# Part15_I2C_LED.net
KiCad netlist of a schematic drawn in Altium Designer
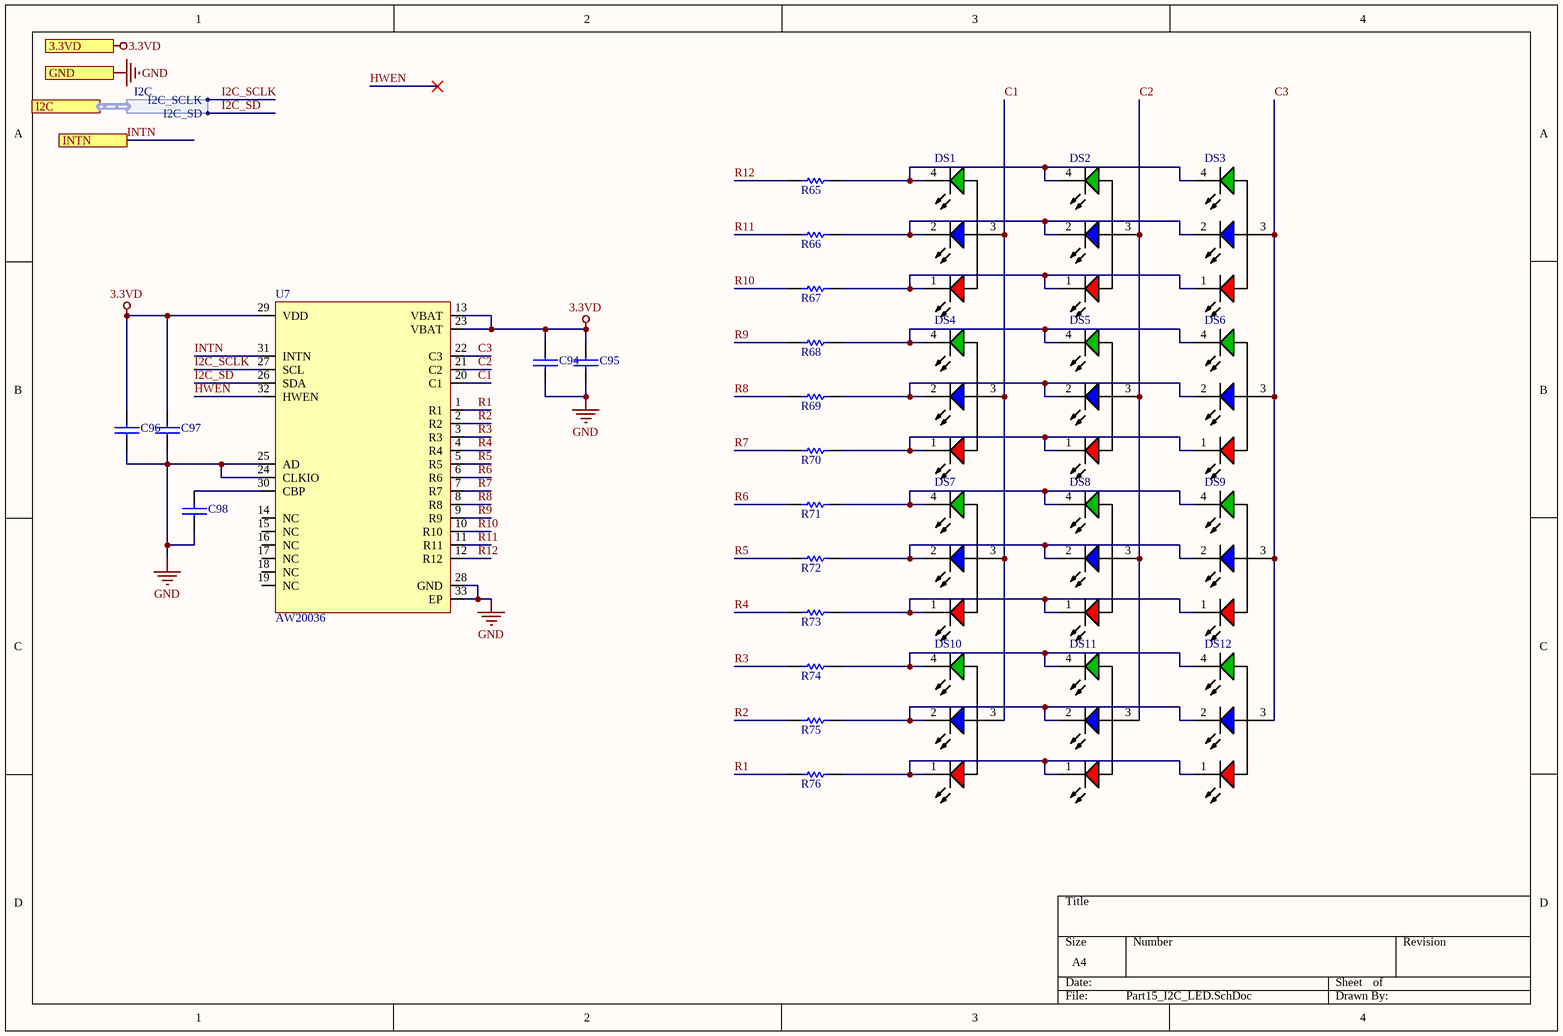
[diagram p0: Part15_I2C_LED.SchDoc]

(export (version "E")
  (design (tool "Eeschema 10.0.6"))
  (components
    (comp (ref "C94")
      (value "100nF")
      (footprint "0402C")
      (description "无极性电容")
      (libsource (lib "电容") (part "CAP"))
    )
    (comp (ref "C95")
      (value "4.7uF")
      (footprint "0402C")
      (description "无极性电容")
      (libsource (lib "电容") (part "CAP"))
    )
    (comp (ref "C96")
      (value "1uF")
      (footprint "0402C")
      (description "无极性电容")
      (libsource (lib "电容") (part "CAP"))
    )
    (comp (ref "C97")
      (value "100nF")
      (footprint "0402C")
      (description "无极性电容")
      (libsource (lib "电容") (part "CAP"))
    )
    (comp (ref "C98")
      (value "1uF")
      (footprint "0402C")
      (description "无极性电容")
      (libsource (lib "电容") (part "CAP"))
    )
    (comp (ref "DS1")
      (value "CLVBA-FKA-CAEDH8BBB7A363")
      (footprint "RGB_LED")
      (description "3-in-1 SMD Led, 1.9 V Red, 3 V Green, 3 V Blue, -40 to 100 degC, 4-Pin PLCC, RoHS, Reel")
      (fields (field (name "MANUFACTURER") "Cree,Inc."))
      (libsource (lib "MT7688_Lib") (part "LED-RGB-KCKK-4"))
    )
    (comp (ref "DS2")
      (value "CLVBA-FKA-CAEDH8BBB7A363")
      (footprint "RGB_LED")
      (description "3-in-1 SMD Led, 1.9 V Red, 3 V Green, 3 V Blue, -40 to 100 degC, 4-Pin PLCC, RoHS, Reel")
      (fields (field (name "MANUFACTURER") "Cree,Inc."))
      (libsource (lib "MT7688_Lib") (part "LED-RGB-KCKK-4"))
    )
    (comp (ref "DS3")
      (value "CLVBA-FKA-CAEDH8BBB7A363")
      (footprint "RGB_LED")
      (description "3-in-1 SMD Led, 1.9 V Red, 3 V Green, 3 V Blue, -40 to 100 degC, 4-Pin PLCC, RoHS, Reel")
      (fields (field (name "MANUFACTURER") "Cree,Inc."))
      (libsource (lib "MT7688_Lib") (part "LED-RGB-KCKK-4"))
    )
    (comp (ref "DS4")
      (value "CLVBA-FKA-CAEDH8BBB7A363")
      (footprint "RGB_LED")
      (description "3-in-1 SMD Led, 1.9 V Red, 3 V Green, 3 V Blue, -40 to 100 degC, 4-Pin PLCC, RoHS, Reel")
      (fields (field (name "MANUFACTURER") "Cree,Inc."))
      (libsource (lib "MT7688_Lib") (part "LED-RGB-KCKK-4"))
    )
    (comp (ref "DS5")
      (value "CLVBA-FKA-CAEDH8BBB7A363")
      (footprint "RGB_LED")
      (description "3-in-1 SMD Led, 1.9 V Red, 3 V Green, 3 V Blue, -40 to 100 degC, 4-Pin PLCC, RoHS, Reel")
      (fields (field (name "MANUFACTURER") "Cree,Inc."))
      (libsource (lib "MT7688_Lib") (part "LED-RGB-KCKK-4"))
    )
    (comp (ref "DS6")
      (value "CLVBA-FKA-CAEDH8BBB7A363")
      (footprint "RGB_LED")
      (description "3-in-1 SMD Led, 1.9 V Red, 3 V Green, 3 V Blue, -40 to 100 degC, 4-Pin PLCC, RoHS, Reel")
      (fields (field (name "MANUFACTURER") "Cree,Inc."))
      (libsource (lib "MT7688_Lib") (part "LED-RGB-KCKK-4"))
    )
    (comp (ref "DS7")
      (value "CLVBA-FKA-CAEDH8BBB7A363")
      (footprint "RGB_LED")
      (description "3-in-1 SMD Led, 1.9 V Red, 3 V Green, 3 V Blue, -40 to 100 degC, 4-Pin PLCC, RoHS, Reel")
      (fields (field (name "MANUFACTURER") "Cree,Inc."))
      (libsource (lib "MT7688_Lib") (part "LED-RGB-KCKK-4"))
    )
    (comp (ref "DS8")
      (value "CLVBA-FKA-CAEDH8BBB7A363")
      (footprint "RGB_LED")
      (description "3-in-1 SMD Led, 1.9 V Red, 3 V Green, 3 V Blue, -40 to 100 degC, 4-Pin PLCC, RoHS, Reel")
      (fields (field (name "MANUFACTURER") "Cree,Inc."))
      (libsource (lib "MT7688_Lib") (part "LED-RGB-KCKK-4"))
    )
    (comp (ref "DS9")
      (value "CLVBA-FKA-CAEDH8BBB7A363")
      (footprint "RGB_LED")
      (description "3-in-1 SMD Led, 1.9 V Red, 3 V Green, 3 V Blue, -40 to 100 degC, 4-Pin PLCC, RoHS, Reel")
      (fields (field (name "MANUFACTURER") "Cree,Inc."))
      (libsource (lib "MT7688_Lib") (part "LED-RGB-KCKK-4"))
    )
    (comp (ref "DS10")
      (value "CLVBA-FKA-CAEDH8BBB7A363")
      (footprint "RGB_LED")
      (description "3-in-1 SMD Led, 1.9 V Red, 3 V Green, 3 V Blue, -40 to 100 degC, 4-Pin PLCC, RoHS, Reel")
      (fields (field (name "MANUFACTURER") "Cree,Inc."))
      (libsource (lib "MT7688_Lib") (part "LED-RGB-KCKK-4"))
    )
    (comp (ref "DS11")
      (value "CLVBA-FKA-CAEDH8BBB7A363")
      (footprint "RGB_LED")
      (description "3-in-1 SMD Led, 1.9 V Red, 3 V Green, 3 V Blue, -40 to 100 degC, 4-Pin PLCC, RoHS, Reel")
      (fields (field (name "MANUFACTURER") "Cree,Inc."))
      (libsource (lib "MT7688_Lib") (part "LED-RGB-KCKK-4"))
    )
    (comp (ref "DS12")
      (value "CLVBA-FKA-CAEDH8BBB7A363")
      (footprint "RGB_LED")
      (description "3-in-1 SMD Led, 1.9 V Red, 3 V Green, 3 V Blue, -40 to 100 degC, 4-Pin PLCC, RoHS, Reel")
      (fields (field (name "MANUFACTURER") "Cree,Inc."))
      (libsource (lib "MT7688_Lib") (part "LED-RGB-KCKK-4"))
    )
    (comp (ref "R65") (value "51R") (footprint "0402R") (libsource (lib "电阻") (part "RES")))
    (comp (ref "R66") (value "20R") (footprint "0402R") (libsource (lib "电阻") (part "RES")))
    (comp (ref "R67") (value "20R") (footprint "0402R") (libsource (lib "电阻") (part "RES")))
    (comp (ref "R68") (value "51R") (footprint "0402R") (libsource (lib "电阻") (part "RES")))
    (comp (ref "R69") (value "20R") (footprint "0402R") (libsource (lib "电阻") (part "RES")))
    (comp (ref "R70") (value "20R") (footprint "0402R") (libsource (lib "电阻") (part "RES")))
    (comp (ref "R71") (value "51R") (footprint "0402R") (libsource (lib "电阻") (part "RES")))
    (comp (ref "R72") (value "20R") (footprint "0402R") (libsource (lib "电阻") (part "RES")))
    (comp (ref "R73") (value "20R") (footprint "0402R") (libsource (lib "电阻") (part "RES")))
    (comp (ref "R74") (value "51R") (footprint "0402R") (libsource (lib "电阻") (part "RES")))
    (comp (ref "R75") (value "20R") (footprint "0402R") (libsource (lib "电阻") (part "RES")))
    (comp (ref "R76") (value "20R") (footprint "0402R") (libsource (lib "电阻") (part "RES")))
    (comp (ref "U7")
      (value "AW20036")
      (footprint "QFN40P400X400X80_HS-33N")
      (libsource (lib "MT7688_Lib") (part "AW20036"))
    )
  )
  (nets
    (net (code "2") (name "/C1") (class "Default")
      (node (ref "DS1") (pin "3") (pinfunction "COMMON_3") (pintype "passive"))
      (node (ref "DS10") (pin "3") (pinfunction "COMMON_3") (pintype "passive"))
      (node (ref "DS4") (pin "3") (pinfunction "COMMON_3") (pintype "passive"))
      (node (ref "DS7") (pin "3") (pinfunction "COMMON_3") (pintype "passive"))
      (node (ref "U7") (pin "20") (pinfunction "C1_20") (pintype "passive"))
    )
    (net (code "3") (name "/C2") (class "Default")
      (node (ref "DS11") (pin "3") (pinfunction "COMMON_3") (pintype "passive"))
      (node (ref "DS2") (pin "3") (pinfunction "COMMON_3") (pintype "passive"))
      (node (ref "DS5") (pin "3") (pinfunction "COMMON_3") (pintype "passive"))
      (node (ref "DS8") (pin "3") (pinfunction "COMMON_3") (pintype "passive"))
      (node (ref "U7") (pin "21") (pinfunction "C2_21") (pintype "passive"))
    )
    (net (code "4") (name "/C3") (class "Default")
      (node (ref "DS12") (pin "3") (pinfunction "COMMON_3") (pintype "passive"))
      (node (ref "DS3") (pin "3") (pinfunction "COMMON_3") (pintype "passive"))
      (node (ref "DS6") (pin "3") (pinfunction "COMMON_3") (pintype "passive"))
      (node (ref "DS9") (pin "3") (pinfunction "COMMON_3") (pintype "passive"))
      (node (ref "U7") (pin "22") (pinfunction "C3_22") (pintype "passive"))
    )
    (net (code "5") (name "/HWEN") (class "Default")
      (node (ref "U7") (pin "32") (pinfunction "HWEN_32") (pintype "passive"))
    )
    (net (code "6") (name "/I2C_SCLK") (class "Default")
      (node (ref "U7") (pin "27") (pinfunction "SCL_27") (pintype "passive"))
    )
    (net (code "7") (name "/I2C_SD") (class "Default")
      (node (ref "U7") (pin "26") (pinfunction "SDA_26") (pintype "passive"))
    )
    (net (code "8") (name "/INTN") (class "Default")
      (node (ref "U7") (pin "31") (pinfunction "INTN_31") (pintype "passive"))
    )
    (net (code "9") (name "/R1") (class "Default")
      (node (ref "R76") (pin "1") (pinfunction "1_1") (pintype "passive"))
      (node (ref "U7") (pin "1") (pinfunction "R1_1") (pintype "passive"))
    )
    (net (code "10") (name "/R2") (class "Default")
      (node (ref "R75") (pin "1") (pinfunction "1_1") (pintype "passive"))
      (node (ref "U7") (pin "2") (pinfunction "R2_2") (pintype "passive"))
    )
    (net (code "11") (name "/R3") (class "Default")
      (node (ref "R74") (pin "1") (pinfunction "1_1") (pintype "passive"))
      (node (ref "U7") (pin "3") (pinfunction "R3_3") (pintype "passive"))
    )
    (net (code "12") (name "/R4") (class "Default")
      (node (ref "R73") (pin "1") (pinfunction "1_1") (pintype "passive"))
      (node (ref "U7") (pin "4") (pinfunction "R4_4") (pintype "passive"))
    )
    (net (code "13") (name "/R5") (class "Default")
      (node (ref "R72") (pin "1") (pinfunction "1_1") (pintype "passive"))
      (node (ref "U7") (pin "5") (pinfunction "R5_5") (pintype "passive"))
    )
    (net (code "14") (name "/R6") (class "Default")
      (node (ref "R71") (pin "1") (pinfunction "1_1") (pintype "passive"))
      (node (ref "U7") (pin "6") (pinfunction "R6_6") (pintype "passive"))
    )
    (net (code "15") (name "/R7") (class "Default")
      (node (ref "R70") (pin "1") (pinfunction "1_1") (pintype "passive"))
      (node (ref "U7") (pin "7") (pinfunction "R7_7") (pintype "passive"))
    )
    (net (code "16") (name "/R8") (class "Default")
      (node (ref "R69") (pin "1") (pinfunction "1_1") (pintype "passive"))
      (node (ref "U7") (pin "8") (pinfunction "R8_8") (pintype "passive"))
    )
    (net (code "17") (name "/R9") (class "Default")
      (node (ref "R68") (pin "1") (pinfunction "1_1") (pintype "passive"))
      (node (ref "U7") (pin "9") (pinfunction "R9_9") (pintype "passive"))
    )
    (net (code "18") (name "/R10") (class "Default")
      (node (ref "R67") (pin "1") (pinfunction "1_1") (pintype "passive"))
      (node (ref "U7") (pin "10") (pinfunction "R10_10") (pintype "passive"))
    )
    (net (code "19") (name "/R11") (class "Default")
      (node (ref "R66") (pin "1") (pinfunction "1_1") (pintype "passive"))
      (node (ref "U7") (pin "11") (pinfunction "R11_11") (pintype "passive"))
    )
    (net (code "20") (name "/R12") (class "Default")
      (node (ref "R65") (pin "1") (pinfunction "1_1") (pintype "passive"))
      (node (ref "U7") (pin "12") (pinfunction "R12_12") (pintype "passive"))
    )
    (net (code "22") (name "3.3VD") (class "Default")
      (node (ref "C94") (pin "1") (pinfunction "1_1") (pintype "passive"))
      (node (ref "C95") (pin "1") (pinfunction "1_1") (pintype "passive"))
      (node (ref "C96") (pin "1") (pinfunction "1_1") (pintype "passive"))
      (node (ref "C97") (pin "1") (pinfunction "1_1") (pintype "passive"))
      (node (ref "U7") (pin "13") (pinfunction "VBAT_13") (pintype "passive"))
      (node (ref "U7") (pin "23") (pinfunction "VBAT_23") (pintype "passive"))
      (node (ref "U7") (pin "29") (pinfunction "VDD_29") (pintype "passive"))
    )
    (net (code "23") (name "GND") (class "Default")
      (node (ref "C94") (pin "2") (pinfunction "2_2") (pintype "passive"))
      (node (ref "C95") (pin "2") (pinfunction "2_2") (pintype "passive"))
      (node (ref "C96") (pin "2") (pinfunction "2_2") (pintype "passive"))
      (node (ref "C97") (pin "2") (pinfunction "2_2") (pintype "passive"))
      (node (ref "C98") (pin "2") (pinfunction "2_2") (pintype "passive"))
      (node (ref "U7") (pin "24") (pinfunction "CLKIO_24") (pintype "passive"))
      (node (ref "U7") (pin "25") (pinfunction "AD_25") (pintype "passive"))
      (node (ref "U7") (pin "28") (pinfunction "GND_28") (pintype "passive"))
      (node (ref "U7") (pin "33") (pinfunction "EP_33") (pintype "passive"))
    )
    (net (code "24") (name "Net-(DS1-BLUE)") (class "Default")
      (node (ref "DS1") (pin "2") (pinfunction "BLUE_2") (pintype "passive"))
      (node (ref "DS2") (pin "2") (pinfunction "BLUE_2") (pintype "passive"))
      (node (ref "DS3") (pin "2") (pinfunction "BLUE_2") (pintype "passive"))
      (node (ref "R66") (pin "2") (pinfunction "2_2") (pintype "passive"))
    )
    (net (code "25") (name "Net-(DS1-GREEN)") (class "Default")
      (node (ref "DS1") (pin "4") (pinfunction "GREEN_4") (pintype "passive"))
      (node (ref "DS2") (pin "4") (pinfunction "GREEN_4") (pintype "passive"))
      (node (ref "DS3") (pin "4") (pinfunction "GREEN_4") (pintype "passive"))
      (node (ref "R65") (pin "2") (pinfunction "2_2") (pintype "passive"))
    )
    (net (code "26") (name "Net-(DS1-RED)") (class "Default")
      (node (ref "DS1") (pin "1") (pinfunction "RED_1") (pintype "passive"))
      (node (ref "DS2") (pin "1") (pinfunction "RED_1") (pintype "passive"))
      (node (ref "DS3") (pin "1") (pinfunction "RED_1") (pintype "passive"))
      (node (ref "R67") (pin "2") (pinfunction "2_2") (pintype "passive"))
    )
    (net (code "27") (name "Net-(DS4-BLUE)") (class "Default")
      (node (ref "DS4") (pin "2") (pinfunction "BLUE_2") (pintype "passive"))
      (node (ref "DS5") (pin "2") (pinfunction "BLUE_2") (pintype "passive"))
      (node (ref "DS6") (pin "2") (pinfunction "BLUE_2") (pintype "passive"))
      (node (ref "R69") (pin "2") (pinfunction "2_2") (pintype "passive"))
    )
    (net (code "28") (name "Net-(DS4-GREEN)") (class "Default")
      (node (ref "DS4") (pin "4") (pinfunction "GREEN_4") (pintype "passive"))
      (node (ref "DS5") (pin "4") (pinfunction "GREEN_4") (pintype "passive"))
      (node (ref "DS6") (pin "4") (pinfunction "GREEN_4") (pintype "passive"))
      (node (ref "R68") (pin "2") (pinfunction "2_2") (pintype "passive"))
    )
    (net (code "29") (name "Net-(DS4-RED)") (class "Default")
      (node (ref "DS4") (pin "1") (pinfunction "RED_1") (pintype "passive"))
      (node (ref "DS5") (pin "1") (pinfunction "RED_1") (pintype "passive"))
      (node (ref "DS6") (pin "1") (pinfunction "RED_1") (pintype "passive"))
      (node (ref "R70") (pin "2") (pinfunction "2_2") (pintype "passive"))
    )
    (net (code "30") (name "Net-(DS7-BLUE)") (class "Default")
      (node (ref "DS7") (pin "2") (pinfunction "BLUE_2") (pintype "passive"))
      (node (ref "DS8") (pin "2") (pinfunction "BLUE_2") (pintype "passive"))
      (node (ref "DS9") (pin "2") (pinfunction "BLUE_2") (pintype "passive"))
      (node (ref "R72") (pin "2") (pinfunction "2_2") (pintype "passive"))
    )
    (net (code "31") (name "Net-(DS7-GREEN)") (class "Default")
      (node (ref "DS7") (pin "4") (pinfunction "GREEN_4") (pintype "passive"))
      (node (ref "DS8") (pin "4") (pinfunction "GREEN_4") (pintype "passive"))
      (node (ref "DS9") (pin "4") (pinfunction "GREEN_4") (pintype "passive"))
      (node (ref "R71") (pin "2") (pinfunction "2_2") (pintype "passive"))
    )
    (net (code "32") (name "Net-(DS7-RED)") (class "Default")
      (node (ref "DS7") (pin "1") (pinfunction "RED_1") (pintype "passive"))
      (node (ref "DS8") (pin "1") (pinfunction "RED_1") (pintype "passive"))
      (node (ref "DS9") (pin "1") (pinfunction "RED_1") (pintype "passive"))
      (node (ref "R73") (pin "2") (pinfunction "2_2") (pintype "passive"))
    )
    (net (code "33") (name "Net-(DS10-BLUE)") (class "Default")
      (node (ref "DS10") (pin "2") (pinfunction "BLUE_2") (pintype "passive"))
      (node (ref "DS11") (pin "2") (pinfunction "BLUE_2") (pintype "passive"))
      (node (ref "DS12") (pin "2") (pinfunction "BLUE_2") (pintype "passive"))
      (node (ref "R75") (pin "2") (pinfunction "2_2") (pintype "passive"))
    )
    (net (code "34") (name "Net-(DS10-GREEN)") (class "Default")
      (node (ref "DS10") (pin "4") (pinfunction "GREEN_4") (pintype "passive"))
      (node (ref "DS11") (pin "4") (pinfunction "GREEN_4") (pintype "passive"))
      (node (ref "DS12") (pin "4") (pinfunction "GREEN_4") (pintype "passive"))
      (node (ref "R74") (pin "2") (pinfunction "2_2") (pintype "passive"))
    )
    (net (code "35") (name "Net-(DS10-RED)") (class "Default")
      (node (ref "DS10") (pin "1") (pinfunction "RED_1") (pintype "passive"))
      (node (ref "DS11") (pin "1") (pinfunction "RED_1") (pintype "passive"))
      (node (ref "DS12") (pin "1") (pinfunction "RED_1") (pintype "passive"))
      (node (ref "R76") (pin "2") (pinfunction "2_2") (pintype "passive"))
    )
    (net (code "36") (name "Net-(U7-CBP)") (class "Default")
      (node (ref "C98") (pin "1") (pinfunction "1_1") (pintype "passive"))
      (node (ref "U7") (pin "30") (pinfunction "CBP_30") (pintype "passive"))
    )
    (net (code "37") (name "unconnected-(U7-NC-Pad14)") (class "Default")
      (node (ref "U7") (pin "14") (pinfunction "NC_14") (pintype "passive"))
    )
    (net (code "38") (name "unconnected-(U7-NC-Pad15)") (class "Default")
      (node (ref "U7") (pin "15") (pinfunction "NC_15") (pintype "passive"))
    )
    (net (code "39") (name "unconnected-(U7-NC-Pad16)") (class "Default")
      (node (ref "U7") (pin "16") (pinfunction "NC_16") (pintype "passive"))
    )
    (net (code "40") (name "unconnected-(U7-NC-Pad17)") (class "Default")
      (node (ref "U7") (pin "17") (pinfunction "NC_17") (pintype "passive"))
    )
    (net (code "41") (name "unconnected-(U7-NC-Pad18)") (class "Default")
      (node (ref "U7") (pin "18") (pinfunction "NC_18") (pintype "passive"))
    )
    (net (code "42") (name "unconnected-(U7-NC-Pad19)") (class "Default")
      (node (ref "U7") (pin "19") (pinfunction "NC_19") (pintype "passive"))
    )
  )
)
